# buck.net
KiCad netlist of a schematic drawn in Altium Designer
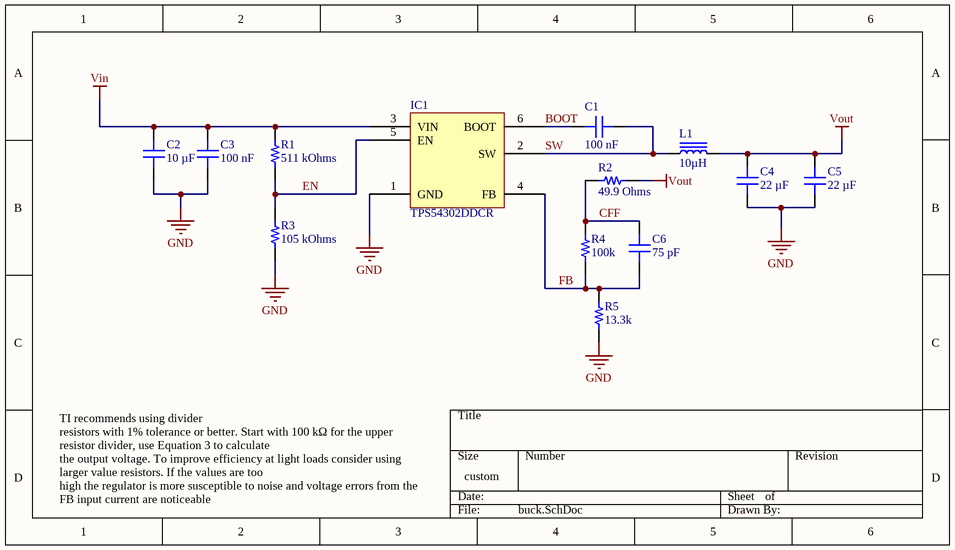
[diagram p0: buck.SchDoc]

(export (version "E")
  (design (tool "Eeschema 10.0.6"))
  (components
    (comp (ref "C1")
      (value "100 nF")
      (footprint "CAP 0603_1608")
      (description "CAP CER 0603 0.1UF 16V X7R 5%")
      (fields (field (name "PART NUMBER") "C0603C104J4RECAUTO") (field (name "MANUFACTURER") "KEMET"))
      (libsource (lib "Celestial Altium Library - altium_library") (part "Capacitor"))
    )
    (comp (ref "C2")
      (value "10 µF")
      (footprint "CAP 0805_2012")
      (description "CAP CER 10UF 10V X7R 0805")
      (fields
        (field (name "PART NUMBER") "C2012X7R1A106K125AE")
        (field (name "MANUFACTURER") "TDK Corporation")
      )
      (libsource (lib "Celestial Altium Library - altium_library") (part "Capacitor"))
    )
    (comp (ref "C3")
      (value "100 nF")
      (footprint "CAP 0603_1608")
      (description "CAP CER 0603 0.1UF 16V X7R 5%")
      (fields (field (name "PART NUMBER") "C0603C104J4RECAUTO") (field (name "MANUFACTURER") "KEMET"))
      (libsource (lib "Celestial Altium Library - altium_library") (part "Capacitor"))
    )
    (comp (ref "C4")
      (value "22 µF")
      (footprint "CAP 0805_2012")
      (description "CAP CER 22UF 16V X5R 0805")
      (fields
        (field (name "PART NUMBER") "CL21A226KOQNNNG")
        (field (name "MANUFACTURER") "Samsung Electro-Mechanics")
      )
      (libsource (lib "Celestial Altium Library - altium_library") (part "Capacitor"))
    )
    (comp (ref "C5")
      (value "22 µF")
      (footprint "CAP 0805_2012")
      (description "CAP CER 22UF 16V X5R 0805")
      (fields
        (field (name "PART NUMBER") "CL21A226KOQNNNG")
        (field (name "MANUFACTURER") "Samsung Electro-Mechanics")
      )
      (libsource (lib "Celestial Altium Library - altium_library") (part "Capacitor"))
    )
    (comp (ref "C6")
      (value "75 pF")
      (footprint "CAP 0603_1608")
      (description "CAP CER 75PF 50V X7R 0603")
      (fields (field (name "PART NUMBER") "C0603C750K5RACAUTO") (field (name "MANUFACTURER") "KEMET"))
      (libsource (lib "Celestial Altium Library - altium_library") (part "Capacitor"))
    )
    (comp (ref "IC1")
      (value "TPS54302DDCR")
      (footprint "TI SOT-23-6 DDC")
      (description "IC REG BUCK ADJ 3A TSOT23-6")
      (fields (field (name "PART NUMBER") "TPS54302DDCT") (field (name "MANUFACTURER") "Texas Instruments"))
      (libsource (lib "Celestial Altium Library - altium_library") (part "TI TPS54302"))
    )
    (comp (ref "L1")
      (value "10µH")
      (footprint "IND 1008_2520")
      (description "FIXED IND 10UH 1A 689 MOHM SMD")
      (fields
        (field (name "PART NUMBER") "1269AS-H-100N=P2")
        (field (name "MANUFACTURER") "Murata Electronics")
      )
      (libsource (lib "Celestial Altium Library - altium_library") (part "Inductor"))
    )
    (comp (ref "R1")
      (value "511 kOhms")
      (footprint "RES 0805_2012")
      (description "RES SMD 511K OHM 0.5% 1/4W 0805")
      (fields
        (field (name "PART NUMBER") "ERJ-PB6D5113V")
        (field (name "MANUFACTURER") "Panasonic Electronic Components")
      )
      (libsource (lib "Celestial Altium Library - altium_library") (part "Resistor"))
    )
    (comp (ref "R2")
      (value "49.9 Ohms")
      (footprint "RES 0805_2012")
      (description "RES SMD 511K OHM 0.5% 1/4W 0805")
      (fields
        (field (name "PART NUMBER") "ERJ-PB6D5113V")
        (field (name "MANUFACTURER") "Panasonic Electronic Components")
      )
      (libsource (lib "Celestial Altium Library - altium_library") (part "Resistor"))
    )
    (comp (ref "R3")
      (value "105 kOhms")
      (footprint "RES 0805_2012")
      (description "RES SMD 511K OHM 0.5% 1/4W 0805")
      (fields
        (field (name "PART NUMBER") "ERJ-PB6D5113V")
        (field (name "MANUFACTURER") "Panasonic Electronic Components")
      )
      (libsource (lib "Celestial Altium Library - altium_library") (part "Resistor"))
    )
    (comp (ref "R4")
      (value "100k")
      (footprint "RES 0805_2012")
      (description "RES SMD 511K OHM 0.5% 1/4W 0805")
      (fields
        (field (name "PART NUMBER") "ERJ-PB6D5113V")
        (field (name "MANUFACTURER") "Panasonic Electronic Components")
      )
      (libsource (lib "Celestial Altium Library - altium_library") (part "Resistor"))
    )
    (comp (ref "R5")
      (value "13.3k")
      (footprint "RES 0805_2012")
      (description "RES SMD 511K OHM 0.5% 1/4W 0805")
      (fields
        (field (name "PART NUMBER") "ERJ-PB6D5113V")
        (field (name "MANUFACTURER") "Panasonic Electronic Components")
      )
      (libsource (lib "Celestial Altium Library - altium_library") (part "Resistor"))
    )
  )
  (nets
    (net (code "1") (name "/BOOT") (class "Default")
      (node (ref "C1") (pin "1") (pinfunction "1_1") (pintype "passive"))
      (node (ref "IC1") (pin "6") (pinfunction "BOOT_6") (pintype "passive"))
    )
    (net (code "2") (name "/CFF") (class "Default")
      (node (ref "C6") (pin "2") (pinfunction "2_2") (pintype "passive"))
      (node (ref "R2") (pin "2") (pinfunction "2_2") (pintype "passive"))
      (node (ref "R4") (pin "1") (pinfunction "1_1") (pintype "passive"))
    )
    (net (code "3") (name "/EN") (class "Default")
      (node (ref "IC1") (pin "5") (pinfunction "EN_5") (pintype "passive"))
      (node (ref "R1") (pin "1") (pinfunction "1_1") (pintype "passive"))
      (node (ref "R3") (pin "1") (pinfunction "1_1") (pintype "passive"))
    )
    (net (code "4") (name "/FB") (class "Default")
      (node (ref "C6") (pin "1") (pinfunction "1_1") (pintype "passive"))
      (node (ref "IC1") (pin "4") (pinfunction "FB_4") (pintype "passive"))
      (node (ref "R4") (pin "2") (pinfunction "2_2") (pintype "passive"))
      (node (ref "R5") (pin "1") (pinfunction "1_1") (pintype "passive"))
    )
    (net (code "5") (name "/SW") (class "Default")
      (node (ref "C1") (pin "2") (pinfunction "2_2") (pintype "passive"))
      (node (ref "IC1") (pin "2") (pinfunction "SW_2") (pintype "passive"))
      (node (ref "L1") (pin "1") (pinfunction "1_1") (pintype "passive"))
    )
    (net (code "6") (name "GND") (class "Default")
      (node (ref "C2") (pin "1") (pinfunction "1_1") (pintype "passive"))
      (node (ref "C3") (pin "1") (pinfunction "1_1") (pintype "passive"))
      (node (ref "C4") (pin "1") (pinfunction "1_1") (pintype "passive"))
      (node (ref "C5") (pin "1") (pinfunction "1_1") (pintype "passive"))
      (node (ref "IC1") (pin "1") (pinfunction "GND_1") (pintype "passive"))
      (node (ref "R3") (pin "2") (pinfunction "2_2") (pintype "passive"))
      (node (ref "R5") (pin "2") (pinfunction "2_2") (pintype "passive"))
    )
    (net (code "7") (name "Vin") (class "Default")
      (node (ref "C2") (pin "2") (pinfunction "2_2") (pintype "passive"))
      (node (ref "C3") (pin "2") (pinfunction "2_2") (pintype "passive"))
      (node (ref "IC1") (pin "3") (pinfunction "VIN_3") (pintype "passive"))
      (node (ref "R1") (pin "2") (pinfunction "2_2") (pintype "passive"))
    )
    (net (code "8") (name "Vout") (class "Default")
      (node (ref "C4") (pin "2") (pinfunction "2_2") (pintype "passive"))
      (node (ref "C5") (pin "2") (pinfunction "2_2") (pintype "passive"))
      (node (ref "L1") (pin "2") (pinfunction "2_2") (pintype "passive"))
      (node (ref "R2") (pin "1") (pinfunction "1_1") (pintype "passive"))
    )
  )
)
